# Pico_2W_and_Sensor.net
KiCad netlist of a schematic drawn in Altium Designer
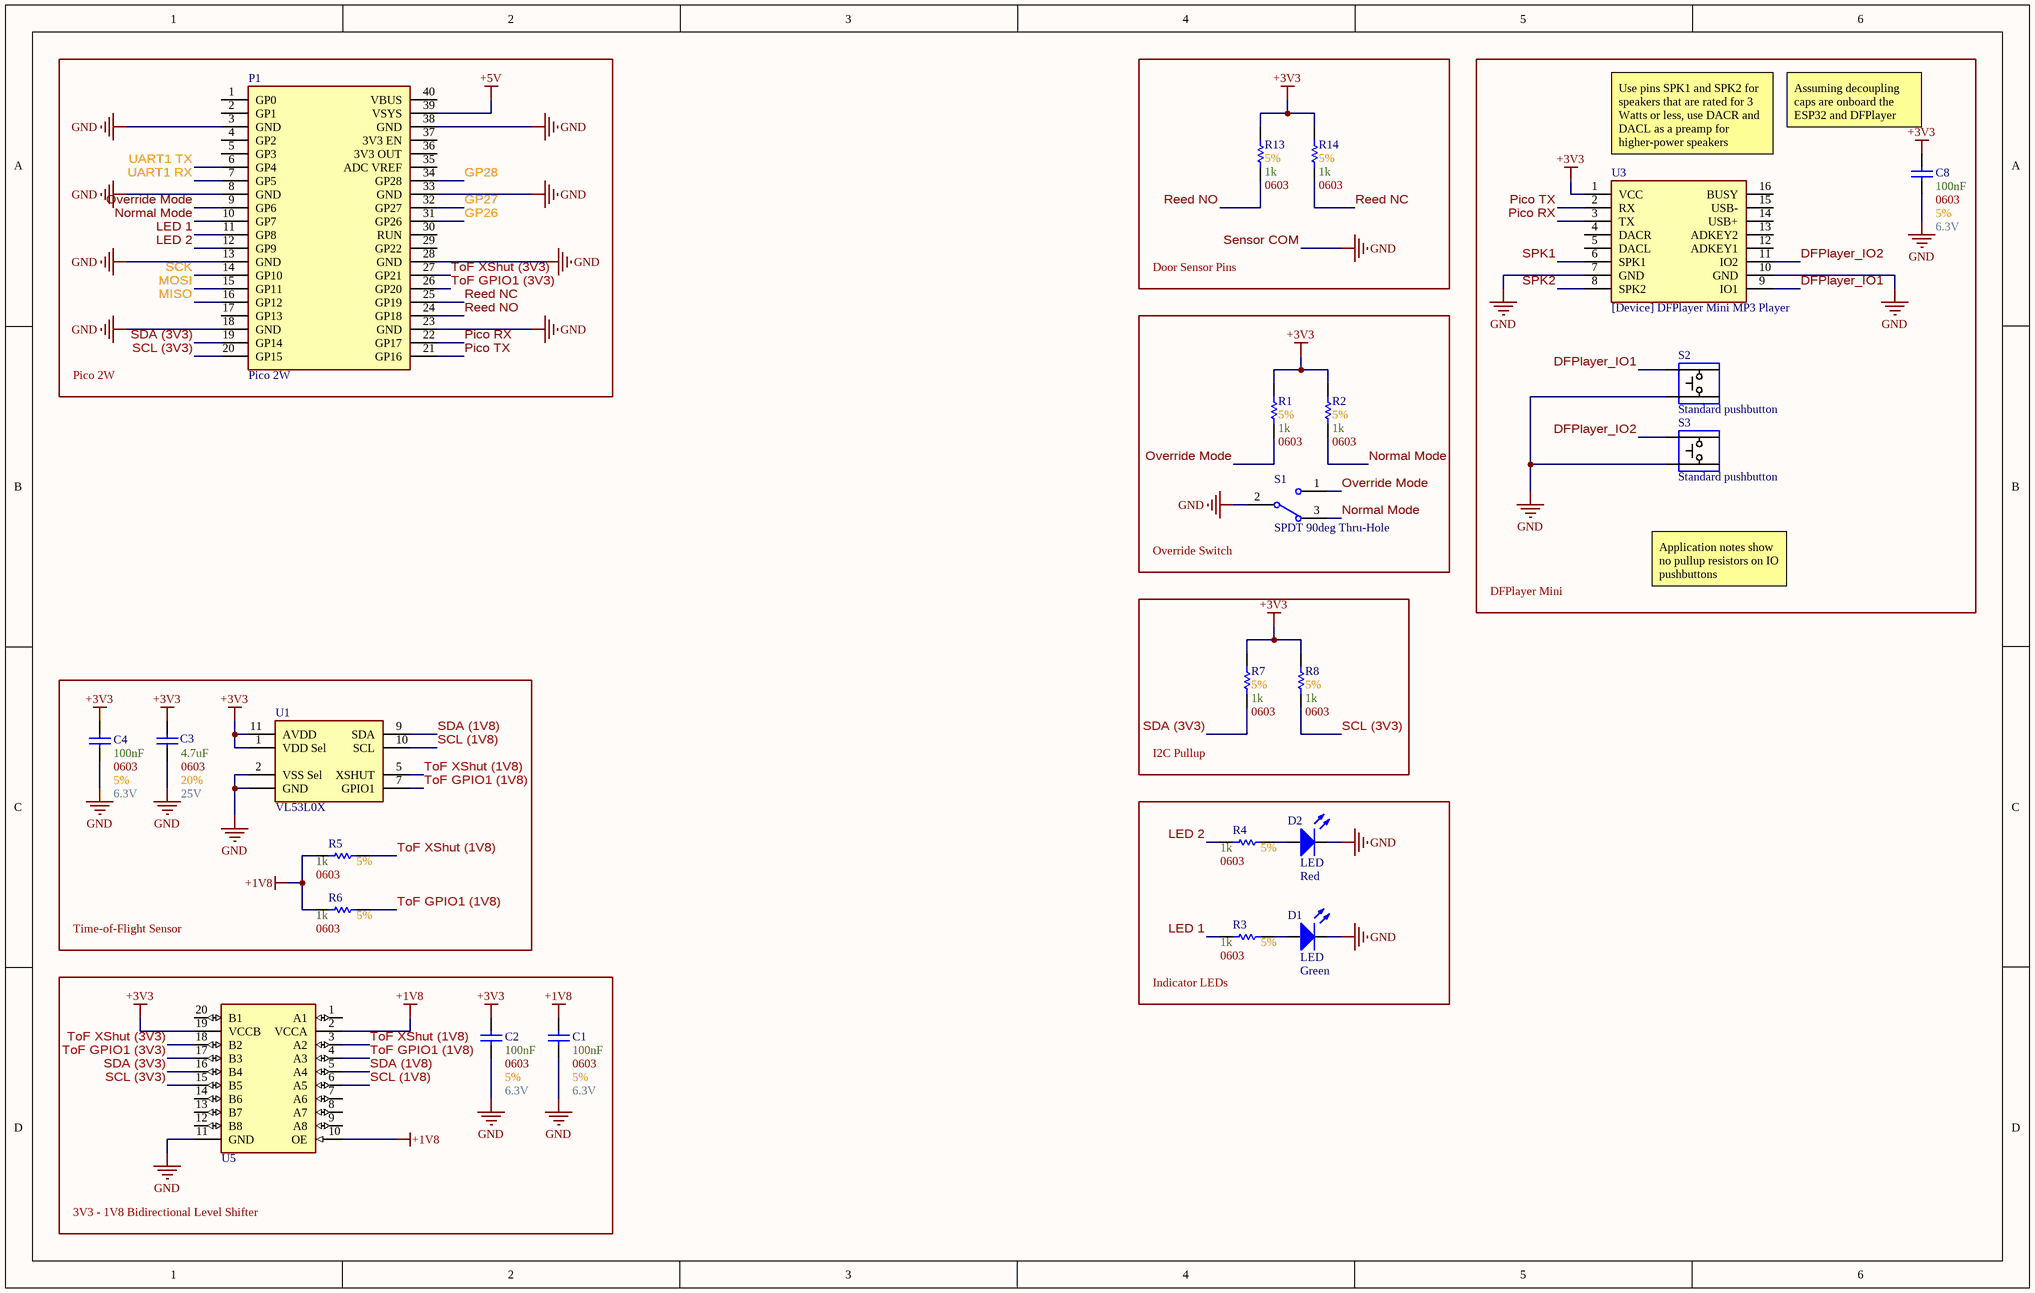
[diagram p0: Pico 2W and Sensor.SchDoc]

(export (version "E")
  (design (tool "Eeschema 10.0.6"))
  (components
    (comp (ref "C1")
      (value "[Cap] SMD Nonpolarized")
      (footprint "[Cap] SMD 0603")
      (fields
        (field (name "SIZE PACKAGE") "0603")
        (field (name "CAPACITANCE") "100nF")
        (field (name "VOLTAGE") "6.3V")
        (field (name "TOLERANCE") "5%")
      )
      (libsource (lib "RADM Components") (part "[Cap] SMD Nonpolarized"))
    )
    (comp (ref "C2")
      (value "[Cap] SMD Nonpolarized")
      (footprint "[Cap] SMD 0603")
      (fields
        (field (name "SIZE PACKAGE") "0603")
        (field (name "CAPACITANCE") "100nF")
        (field (name "VOLTAGE") "6.3V")
        (field (name "TOLERANCE") "5%")
      )
      (libsource (lib "RADM Components") (part "[Cap] SMD Nonpolarized"))
    )
    (comp (ref "C3")
      (value "SMD Nonpolarized")
      (footprint "[Cap] SMD 0603")
      (fields
        (field (name "VOLTAGE") "25V")
        (field (name "TOLERANCE") "20%")
        (field (name "SIZE PACKAGE") "0603")
        (field (name "CAPACITANCE") "4.7uF")
      )
      (libsource (lib "RADM Components") (part "[Cap] SMD Nonpolarized"))
    )
    (comp (ref "C4")
      (value "[Cap] SMD Nonpolarized")
      (footprint "[Cap] SMD 0603")
      (fields
        (field (name "SIZE PACKAGE") "0603")
        (field (name "CAPACITANCE") "100nF")
        (field (name "VOLTAGE") "6.3V")
        (field (name "TOLERANCE") "5%")
      )
      (libsource (lib "RADM Components") (part "[Cap] SMD Nonpolarized"))
    )
    (comp (ref "C8")
      (value "[Cap] SMD Nonpolarized")
      (footprint "[Cap] SMD 0603")
      (fields
        (field (name "SIZE PACKAGE") "0603")
        (field (name "CAPACITANCE") "100nF")
        (field (name "VOLTAGE") "6.3V")
        (field (name "TOLERANCE") "5%")
      )
      (libsource (lib "RADM Components") (part "[Cap] SMD Nonpolarized"))
    )
    (comp (ref "D1")
      (value "LED")
      (footprint "[LED] Thru-Hole, 3mm, Green")
      (description "3mm LED")
      (fields (field (name "COLOR") "Green"))
      (libsource (lib "RADM Components") (part "[LED] Thru-Hole 3mm"))
    )
    (comp (ref "D2")
      (value "LED")
      (footprint "[LED] Thru-Hole, 3mm, Red")
      (description "3mm LED")
      (fields (field (name "COLOR") "Red"))
      (libsource (lib "RADM Components") (part "[LED] Thru-Hole 3mm"))
    )
    (comp (ref "P1")
      (value "Pico 2W")
      (footprint "[Device] RP Pico 2W")
      (libsource (lib "RADM Components") (part "[Device] RP Pico 2W"))
    )
    (comp (ref "R1")
      (value "[Res] SMD Resistor")
      (footprint "[Res] SMD 0603")
      (description "Generic")
      (fields
        (field (name "TOLERANCE") "5%")
        (field (name "RESISTANCE") "1k")
        (field (name "SIZE PACKAGE") "0603")
      )
      (libsource (lib "RADM Components") (part "[Res] SMD Resistor"))
    )
    (comp (ref "R2")
      (value "[Res] SMD Resistor")
      (footprint "[Res] SMD 0603")
      (description "Generic")
      (fields
        (field (name "TOLERANCE") "5%")
        (field (name "RESISTANCE") "1k")
        (field (name "SIZE PACKAGE") "0603")
      )
      (libsource (lib "RADM Components") (part "[Res] SMD Resistor"))
    )
    (comp (ref "R3")
      (value "[Res] SMD Resistor")
      (footprint "[Res] SMD 0603")
      (description "Generic")
      (fields
        (field (name "TOLERANCE") "5%")
        (field (name "RESISTANCE") "1k")
        (field (name "SIZE PACKAGE") "0603")
      )
      (libsource (lib "RADM Components") (part "[Res] SMD Resistor"))
    )
    (comp (ref "R4")
      (value "[Res] SMD Resistor")
      (footprint "[Res] SMD 0603")
      (description "Generic")
      (fields
        (field (name "TOLERANCE") "5%")
        (field (name "RESISTANCE") "1k")
        (field (name "SIZE PACKAGE") "0603")
      )
      (libsource (lib "RADM Components") (part "[Res] SMD Resistor"))
    )
    (comp (ref "R5")
      (value "[Res] SMD Resistor")
      (footprint "[Res] SMD 0603")
      (description "Generic")
      (fields
        (field (name "TOLERANCE") "5%")
        (field (name "RESISTANCE") "1k")
        (field (name "SIZE PACKAGE") "0603")
      )
      (libsource (lib "RADM Components") (part "[Res] SMD Resistor"))
    )
    (comp (ref "R6")
      (value "[Res] SMD Resistor")
      (footprint "[Res] SMD 0603")
      (description "Generic")
      (fields
        (field (name "TOLERANCE") "5%")
        (field (name "RESISTANCE") "1k")
        (field (name "SIZE PACKAGE") "0603")
      )
      (libsource (lib "RADM Components") (part "[Res] SMD Resistor"))
    )
    (comp (ref "R7")
      (value "[Res] SMD Resistor")
      (footprint "[Res] SMD 0603")
      (description "Generic")
      (fields
        (field (name "TOLERANCE") "5%")
        (field (name "RESISTANCE") "1k")
        (field (name "SIZE PACKAGE") "0603")
      )
      (libsource (lib "RADM Components") (part "[Res] SMD Resistor"))
    )
    (comp (ref "R8")
      (value "[Res] SMD Resistor")
      (footprint "[Res] SMD 0603")
      (description "Generic")
      (fields
        (field (name "TOLERANCE") "5%")
        (field (name "RESISTANCE") "1k")
        (field (name "SIZE PACKAGE") "0603")
      )
      (libsource (lib "RADM Components") (part "[Res] SMD Resistor"))
    )
    (comp (ref "R13")
      (value "[Res] SMD Resistor")
      (footprint "[Res] SMD 0603")
      (description "Generic")
      (fields
        (field (name "TOLERANCE") "5%")
        (field (name "RESISTANCE") "1k")
        (field (name "SIZE PACKAGE") "0603")
      )
      (libsource (lib "RADM Components") (part "[Res] SMD Resistor"))
    )
    (comp (ref "R14")
      (value "[Res] SMD Resistor")
      (footprint "[Res] SMD 0603")
      (description "Generic")
      (fields
        (field (name "TOLERANCE") "5%")
        (field (name "RESISTANCE") "1k")
        (field (name "SIZE PACKAGE") "0603")
      )
      (libsource (lib "RADM Components") (part "[Res] SMD Resistor"))
    )
    (comp (ref "S1")
      (value "SPDT 90deg Thru-Hole")
      (footprint "[Switch] SPDT Toggle Switch 90deg")
      (description "100SP1T2B4M6QE")
      (libsource (lib "RADM Components") (part "[Switch] SPDT Toggle Switch 90deg"))
    )
    (comp (ref "S2")
      (value "Standard pushbutton")
      (footprint "[Switch] Pushbutton")
      (libsource (lib "RADM Components") (part "[Switch] Pushbutton"))
    )
    (comp (ref "S3")
      (value "Standard pushbutton")
      (footprint "[Switch] Pushbutton")
      (libsource (lib "RADM Components") (part "[Switch] Pushbutton"))
    )
    (comp (ref "U1")
      (value "VL53L0X")
      (footprint "[Device] Time-of-Flight Sensor")
      (description "VL53L0CXV0DH/1")
      (libsource (lib "RADM Components") (part "[Device] Time-of-Flight Sensor"))
    )
    (comp (ref "U3")
      (value "[Device] DFPlayer Mini MP3 Player")
      (footprint "[Device] DFPlayer Mini MP3 Player")
      (libsource (lib "RADM Components") (part "[Device] DFPlayer Mini MP3 Player"))
    )
    (comp (ref "U5")
      (value "[IC] Level Shifter (2)")
      (footprint "[IC] Level Shifter (2)")
      (description "TXS0108EQPWRQ1")
      (libsource (lib "RADM Components") (part "[IC] Level Shifter (2)"))
    )
  )
  (nets
    (net (code "1") (name "+1V8") (class "Default")
      (node (ref "C1") (pin "2") (pinfunction "2_2") (pintype "passive"))
      (node (ref "R5") (pin "2") (pinfunction "2_2") (pintype "passive"))
      (node (ref "R6") (pin "2") (pinfunction "2_2") (pintype "passive"))
      (node (ref "U5") (pin "10") (pinfunction "OE_10") (pintype "input"))
      (node (ref "U5") (pin "2") (pinfunction "VCCA_2") (pintype "power_in"))
    )
    (net (code "2") (name "+3V3") (class "Default")
      (node (ref "C2") (pin "2") (pinfunction "2_2") (pintype "passive"))
      (node (ref "C3") (pin "2") (pinfunction "2_2") (pintype "passive"))
      (node (ref "C4") (pin "2") (pinfunction "2_2") (pintype "passive"))
      (node (ref "C8") (pin "2") (pinfunction "2_2") (pintype "passive"))
      (node (ref "R1") (pin "1") (pinfunction "1_1") (pintype "passive"))
      (node (ref "R13") (pin "1") (pinfunction "1_1") (pintype "passive"))
      (node (ref "R14") (pin "1") (pinfunction "1_1") (pintype "passive"))
      (node (ref "R2") (pin "1") (pinfunction "1_1") (pintype "passive"))
      (node (ref "R7") (pin "1") (pinfunction "1_1") (pintype "passive"))
      (node (ref "R8") (pin "1") (pinfunction "1_1") (pintype "passive"))
      (node (ref "U1") (pin "1") (pinfunction "VDD_Sel_1") (pintype "power_in"))
      (node (ref "U1") (pin "11") (pinfunction "AVDD_11") (pintype "power_in"))
      (node (ref "U3") (pin "1") (pinfunction "VCC_1") (pintype "power_in"))
      (node (ref "U5") (pin "19") (pinfunction "VCCB_19") (pintype "power_in"))
    )
    (net (code "3") (name "+5V") (class "Default")
      (node (ref "P1") (pin "39") (pinfunction "VSYS_39") (pintype "passive"))
    )
    (net (code "4") (name "/DFPlayer_IO1") (class "Default")
      (node (ref "S2") (pin "1") (pintype "power_in"))
      (node (ref "U3") (pin "9") (pinfunction "IO1_9") (pintype "power_in"))
    )
    (net (code "5") (name "/DFPlayer_IO2") (class "Default")
      (node (ref "S3") (pin "1") (pintype "power_in"))
      (node (ref "U3") (pin "11") (pinfunction "IO2_11") (pintype "power_in"))
    )
    (net (code "6") (name "/GP26") (class "Default")
      (node (ref "P1") (pin "31") (pinfunction "GP26_31") (pintype "passive"))
    )
    (net (code "7") (name "/GP27") (class "Default")
      (node (ref "P1") (pin "32") (pinfunction "GP27_32") (pintype "passive"))
    )
    (net (code "8") (name "/GP28") (class "Default")
      (node (ref "P1") (pin "34") (pinfunction "GP28_34") (pintype "passive"))
    )
    (net (code "9") (name "/LED 1") (class "Default")
      (node (ref "P1") (pin "11") (pinfunction "GP8_11") (pintype "passive"))
      (node (ref "R3") (pin "2") (pinfunction "2_2") (pintype "passive"))
    )
    (net (code "10") (name "/LED 2") (class "Default")
      (node (ref "P1") (pin "12") (pinfunction "GP9_12") (pintype "passive"))
      (node (ref "R4") (pin "2") (pinfunction "2_2") (pintype "passive"))
    )
    (net (code "11") (name "/MISO") (class "Default")
      (node (ref "P1") (pin "16") (pinfunction "GP12_16") (pintype "passive"))
    )
    (net (code "12") (name "/MOSI") (class "Default")
      (node (ref "P1") (pin "15") (pinfunction "GP11_15") (pintype "passive"))
    )
    (net (code "13") (name "/Normal Mode") (class "Default")
      (node (ref "P1") (pin "10") (pinfunction "GP7_10") (pintype "passive"))
      (node (ref "R2") (pin "2") (pinfunction "2_2") (pintype "passive"))
      (node (ref "S1") (pin "3") (pinfunction "3_3") (pintype "passive"))
    )
    (net (code "14") (name "/Override Mode") (class "Default")
      (node (ref "P1") (pin "9") (pinfunction "GP6_9") (pintype "passive"))
      (node (ref "R1") (pin "2") (pinfunction "2_2") (pintype "passive"))
      (node (ref "S1") (pin "1") (pinfunction "1_1") (pintype "passive"))
    )
    (net (code "15") (name "/Pico RX") (class "Default")
      (node (ref "P1") (pin "22") (pinfunction "GP17_22") (pintype "passive"))
      (node (ref "U3") (pin "3") (pinfunction "TX_3") (pintype "power_in"))
    )
    (net (code "16") (name "/Pico TX") (class "Default")
      (node (ref "P1") (pin "21") (pinfunction "GP16_21") (pintype "passive"))
      (node (ref "U3") (pin "2") (pinfunction "RX_2") (pintype "power_in"))
    )
    (net (code "17") (name "/Reed NC") (class "Default")
      (node (ref "P1") (pin "25") (pinfunction "GP19_25") (pintype "passive"))
      (node (ref "R14") (pin "2") (pinfunction "2_2") (pintype "passive"))
    )
    (net (code "18") (name "/Reed NO") (class "Default")
      (node (ref "P1") (pin "24") (pinfunction "GP18_24") (pintype "passive"))
      (node (ref "R13") (pin "2") (pinfunction "2_2") (pintype "passive"))
    )
    (net (code "19") (name "/SCK") (class "Default")
      (node (ref "P1") (pin "14") (pinfunction "GP10_14") (pintype "passive"))
    )
    (net (code "20") (name "/SCL (1V8)") (class "Default")
      (node (ref "U1") (pin "10") (pinfunction "SCL_10") (pintype "passive"))
      (node (ref "U5") (pin "6") (pinfunction "A5_6") (pintype "bidirectional"))
    )
    (net (code "21") (name "/SCL (3V3)") (class "Default")
      (node (ref "P1") (pin "20") (pinfunction "GP15_20") (pintype "passive"))
      (node (ref "R8") (pin "2") (pinfunction "2_2") (pintype "passive"))
      (node (ref "U5") (pin "15") (pinfunction "B5_15") (pintype "bidirectional"))
    )
    (net (code "22") (name "/SDA (1V8)") (class "Default")
      (node (ref "U1") (pin "9") (pinfunction "SDA_9") (pintype "passive"))
      (node (ref "U5") (pin "5") (pinfunction "A4_5") (pintype "bidirectional"))
    )
    (net (code "23") (name "/SDA (3V3)") (class "Default")
      (node (ref "P1") (pin "19") (pinfunction "GP14_19") (pintype "passive"))
      (node (ref "R7") (pin "2") (pinfunction "2_2") (pintype "passive"))
      (node (ref "U5") (pin "16") (pinfunction "B4_16") (pintype "bidirectional"))
    )
    (net (code "24") (name "/SPK1") (class "Default")
      (node (ref "U3") (pin "6") (pinfunction "SPK1_6") (pintype "power_in"))
    )
    (net (code "25") (name "/SPK2") (class "Default")
      (node (ref "U3") (pin "8") (pinfunction "SPK2_8") (pintype "power_in"))
    )
    (net (code "26") (name "/ToF GPIO1 (1V8)") (class "Default")
      (node (ref "R6") (pin "1") (pinfunction "1_1") (pintype "passive"))
      (node (ref "U1") (pin "7") (pinfunction "GPIO1_7") (pintype "passive"))
      (node (ref "U5") (pin "4") (pinfunction "A3_4") (pintype "bidirectional"))
    )
    (net (code "27") (name "/ToF GPIO1 (3V3)") (class "Default")
      (node (ref "P1") (pin "26") (pinfunction "GP20_26") (pintype "passive"))
      (node (ref "U5") (pin "17") (pinfunction "B3_17") (pintype "bidirectional"))
    )
    (net (code "28") (name "/ToF XShut (1V8)") (class "Default")
      (node (ref "R5") (pin "1") (pinfunction "1_1") (pintype "passive"))
      (node (ref "U1") (pin "5") (pinfunction "XSHUT_5") (pintype "passive"))
      (node (ref "U5") (pin "3") (pinfunction "A2_3") (pintype "bidirectional"))
    )
    (net (code "29") (name "/ToF XShut (3V3)") (class "Default")
      (node (ref "P1") (pin "27") (pinfunction "GP21_27") (pintype "passive"))
      (node (ref "U5") (pin "18") (pinfunction "B2_18") (pintype "bidirectional"))
    )
    (net (code "30") (name "/UART1 RX") (class "Default")
      (node (ref "P1") (pin "7") (pinfunction "GP5_7") (pintype "passive"))
    )
    (net (code "31") (name "/UART1 TX") (class "Default")
      (node (ref "P1") (pin "6") (pinfunction "GP4_6") (pintype "passive"))
    )
    (net (code "32") (name "GND") (class "Default")
      (node (ref "C1") (pin "1") (pinfunction "1_1") (pintype "passive"))
      (node (ref "C2") (pin "1") (pinfunction "1_1") (pintype "passive"))
      (node (ref "C3") (pin "1") (pinfunction "1_1") (pintype "passive"))
      (node (ref "C4") (pin "1") (pinfunction "1_1") (pintype "passive"))
      (node (ref "C8") (pin "1") (pinfunction "1_1") (pintype "passive"))
      (node (ref "D1") (pin "2") (pinfunction "K_2") (pintype "passive"))
      (node (ref "D2") (pin "2") (pinfunction "K_2") (pintype "passive"))
      (node (ref "P1") (pin "13") (pinfunction "GND_13") (pintype "passive"))
      (node (ref "P1") (pin "18") (pinfunction "GND_18") (pintype "passive"))
      (node (ref "P1") (pin "23") (pinfunction "GND_23") (pintype "passive"))
      (node (ref "P1") (pin "28") (pinfunction "GND_28") (pintype "passive"))
      (node (ref "P1") (pin "3") (pinfunction "GND_3") (pintype "passive"))
      (node (ref "P1") (pin "33") (pinfunction "GND_33") (pintype "passive"))
      (node (ref "P1") (pin "38") (pinfunction "GND_38") (pintype "passive"))
      (node (ref "P1") (pin "8") (pinfunction "GND_8") (pintype "passive"))
      (node (ref "S1") (pin "2") (pinfunction "2_2") (pintype "passive"))
      (node (ref "S2") (pin "2") (pintype "power_in"))
      (node (ref "S3") (pin "2") (pintype "power_in"))
      (node (ref "U1") (pin "2") (pinfunction "VSS_Sel_2") (pintype "power_in"))
      (node (ref "U1") (pin "GND") (pinfunction "GND_GND") (pintype "power_in"))
      (node (ref "U3") (pin "10") (pinfunction "GND_10") (pintype "power_in"))
      (node (ref "U3") (pin "7") (pinfunction "GND_7") (pintype "power_in"))
      (node (ref "U5") (pin "11") (pinfunction "GND_11") (pintype "power_in"))
    )
    (net (code "33") (name "Net-(D1-A)") (class "Default")
      (node (ref "D1") (pin "1") (pinfunction "A_1") (pintype "passive"))
      (node (ref "R3") (pin "1") (pinfunction "1_1") (pintype "passive"))
    )
    (net (code "34") (name "Net-(D2-A)") (class "Default")
      (node (ref "D2") (pin "1") (pinfunction "A_1") (pintype "passive"))
      (node (ref "R4") (pin "1") (pinfunction "1_1") (pintype "passive"))
    )
    (net (code "35") (name "unconnected-(P1-3V3_EN-Pad37)") (class "Default")
      (node (ref "P1") (pin "37") (pinfunction "3V3_EN_37") (pintype "passive"))
    )
    (net (code "36") (name "unconnected-(P1-3V3_OUT-Pad36)") (class "Default")
      (node (ref "P1") (pin "36") (pinfunction "3V3_OUT_36") (pintype "passive"))
    )
    (net (code "37") (name "unconnected-(P1-ADC_VREF-Pad35)") (class "Default")
      (node (ref "P1") (pin "35") (pinfunction "ADC_VREF_35") (pintype "passive"))
    )
    (net (code "38") (name "unconnected-(P1-GP0-Pad1)") (class "Default")
      (node (ref "P1") (pin "1") (pinfunction "GP0_1") (pintype "passive"))
    )
    (net (code "39") (name "unconnected-(P1-GP1-Pad2)") (class "Default")
      (node (ref "P1") (pin "2") (pinfunction "GP1_2") (pintype "passive"))
    )
    (net (code "40") (name "unconnected-(P1-GP2-Pad4)") (class "Default")
      (node (ref "P1") (pin "4") (pinfunction "GP2_4") (pintype "passive"))
    )
    (net (code "41") (name "unconnected-(P1-GP3-Pad5)") (class "Default")
      (node (ref "P1") (pin "5") (pinfunction "GP3_5") (pintype "passive"))
    )
    (net (code "42") (name "unconnected-(P1-GP13-Pad17)") (class "Default")
      (node (ref "P1") (pin "17") (pinfunction "GP13_17") (pintype "passive"))
    )
    (net (code "43") (name "unconnected-(P1-GP22-Pad29)") (class "Default")
      (node (ref "P1") (pin "29") (pinfunction "GP22_29") (pintype "passive"))
    )
    (net (code "44") (name "unconnected-(P1-RUN-Pad30)") (class "Default")
      (node (ref "P1") (pin "30") (pinfunction "RUN_30") (pintype "passive"))
    )
    (net (code "45") (name "unconnected-(P1-VBUS-Pad40)") (class "Default")
      (node (ref "P1") (pin "40") (pinfunction "VBUS_40") (pintype "passive"))
    )
    (net (code "46") (name "unconnected-(U3-ADKEY1-Pad12)") (class "Default")
      (node (ref "U3") (pin "12") (pinfunction "ADKEY1_12") (pintype "power_in"))
    )
    (net (code "47") (name "unconnected-(U3-ADKEY2-Pad13)") (class "Default")
      (node (ref "U3") (pin "13") (pinfunction "ADKEY2_13") (pintype "power_in"))
    )
    (net (code "48") (name "unconnected-(U3-BUSY-Pad16)") (class "Default")
      (node (ref "U3") (pin "16") (pinfunction "BUSY_16") (pintype "power_in"))
    )
    (net (code "49") (name "unconnected-(U3-DACL-Pad5)") (class "Default")
      (node (ref "U3") (pin "5") (pinfunction "DACL_5") (pintype "power_in"))
    )
    (net (code "50") (name "unconnected-(U3-DACR-Pad4)") (class "Default")
      (node (ref "U3") (pin "4") (pinfunction "DACR_4") (pintype "power_in"))
    )
    (net (code "51") (name "unconnected-(U3-USB+-Pad14)") (class "Default")
      (node (ref "U3") (pin "14") (pinfunction "USB+_14") (pintype "power_in"))
    )
    (net (code "52") (name "unconnected-(U3-USB--Pad15)") (class "Default")
      (node (ref "U3") (pin "15") (pinfunction "USB-_15") (pintype "power_in"))
    )
    (net (code "53") (name "unconnected-(U5-A1-Pad1)") (class "Default")
      (node (ref "U5") (pin "1") (pinfunction "A1_1") (pintype "bidirectional"))
    )
    (net (code "54") (name "unconnected-(U5-A6-Pad7)") (class "Default")
      (node (ref "U5") (pin "7") (pinfunction "A6_7") (pintype "bidirectional"))
    )
    (net (code "55") (name "unconnected-(U5-A7-Pad8)") (class "Default")
      (node (ref "U5") (pin "8") (pinfunction "A7_8") (pintype "bidirectional"))
    )
    (net (code "56") (name "unconnected-(U5-A8-Pad9)") (class "Default")
      (node (ref "U5") (pin "9") (pinfunction "A8_9") (pintype "bidirectional"))
    )
    (net (code "57") (name "unconnected-(U5-B1-Pad20)") (class "Default")
      (node (ref "U5") (pin "20") (pinfunction "B1_20") (pintype "bidirectional"))
    )
    (net (code "58") (name "unconnected-(U5-B6-Pad14)") (class "Default")
      (node (ref "U5") (pin "14") (pinfunction "B6_14") (pintype "bidirectional"))
    )
    (net (code "59") (name "unconnected-(U5-B7-Pad13)") (class "Default")
      (node (ref "U5") (pin "13") (pinfunction "B7_13") (pintype "bidirectional"))
    )
    (net (code "60") (name "unconnected-(U5-B8-Pad12)") (class "Default")
      (node (ref "U5") (pin "12") (pinfunction "B8_12") (pintype "bidirectional"))
    )
  )
)
